# LwIP.net
KiCad netlist of a schematic drawn in Altium Designer
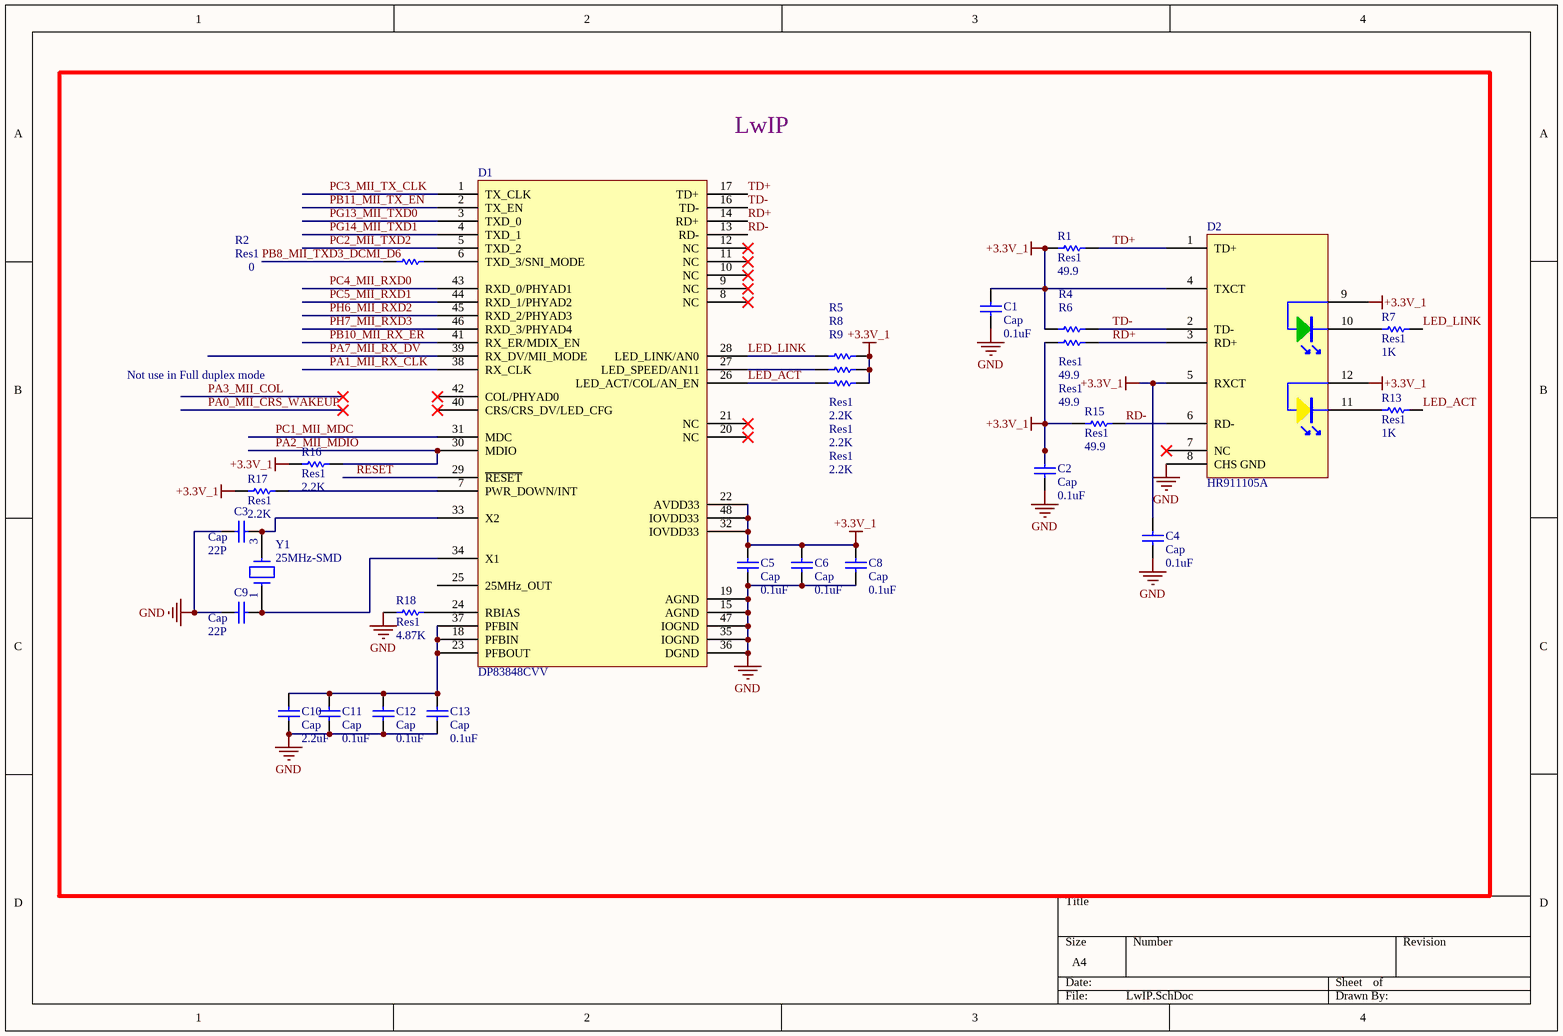
[diagram p0: LwIP.SchDoc]

(export (version "E")
  (design (tool "Eeschema 10.0.6"))
  (components
    (comp (ref "C1")
      (value "Cap")
      (footprint "0805_C")
      (description "Capacitor")
      (fields (field (name "ALTIUM_VALUE") "0.1uF") (field (name "PUBLISHER") "Altium Limited"))
      (libsource (lib "Miscellaneous Devices") (part "Cap"))
    )
    (comp (ref "C2")
      (value "Cap")
      (footprint "0805_C")
      (description "Capacitor")
      (fields (field (name "ALTIUM_VALUE") "0.1uF") (field (name "PUBLISHER") "Altium Limited"))
      (libsource (lib "Miscellaneous Devices") (part "Cap"))
    )
    (comp (ref "C3")
      (value "Cap")
      (footprint "0805_C")
      (description "Capacitor")
      (fields (field (name "ALTIUM_VALUE") "22P") (field (name "PUBLISHER") "Altium Limited"))
      (libsource (lib "Miscellaneous Devices") (part "Cap"))
    )
    (comp (ref "C4")
      (value "Cap")
      (footprint "0805_C")
      (description "Capacitor")
      (fields (field (name "ALTIUM_VALUE") "0.1uF") (field (name "PUBLISHER") "Altium Limited"))
      (libsource (lib "Miscellaneous Devices") (part "Cap"))
    )
    (comp (ref "C5")
      (value "Cap")
      (footprint "0805_C")
      (description "Capacitor")
      (fields (field (name "ALTIUM_VALUE") "0.1uF") (field (name "PUBLISHER") "Altium Limited"))
      (libsource (lib "Miscellaneous Devices") (part "Cap"))
    )
    (comp (ref "C6")
      (value "Cap")
      (footprint "0805_C")
      (description "Capacitor")
      (fields (field (name "ALTIUM_VALUE") "0.1uF") (field (name "PUBLISHER") "Altium Limited"))
      (libsource (lib "Miscellaneous Devices") (part "Cap"))
    )
    (comp (ref "C8")
      (value "Cap")
      (footprint "0805_C")
      (description "Capacitor")
      (fields (field (name "ALTIUM_VALUE") "0.1uF") (field (name "PUBLISHER") "Altium Limited"))
      (libsource (lib "Miscellaneous Devices") (part "Cap"))
    )
    (comp (ref "C9")
      (value "Cap")
      (footprint "0805_C")
      (description "Capacitor")
      (fields (field (name "ALTIUM_VALUE") "22P") (field (name "PUBLISHER") "Altium Limited"))
      (libsource (lib "Miscellaneous Devices") (part "Cap"))
    )
    (comp (ref "C10")
      (value "Cap")
      (footprint "0805_C")
      (description "Capacitor")
      (fields (field (name "ALTIUM_VALUE") "2.2uF") (field (name "PUBLISHER") "Altium Limited"))
      (libsource (lib "Miscellaneous Devices") (part "Cap"))
    )
    (comp (ref "C11")
      (value "Cap")
      (footprint "0805_C")
      (description "Capacitor")
      (fields (field (name "ALTIUM_VALUE") "0.1uF") (field (name "PUBLISHER") "Altium Limited"))
      (libsource (lib "Miscellaneous Devices") (part "Cap"))
    )
    (comp (ref "C12")
      (value "Cap")
      (footprint "0805_C")
      (description "Capacitor")
      (fields (field (name "ALTIUM_VALUE") "0.1uF") (field (name "PUBLISHER") "Altium Limited"))
      (libsource (lib "Miscellaneous Devices") (part "Cap"))
    )
    (comp (ref "C13")
      (value "Cap")
      (footprint "0805_C")
      (description "Capacitor")
      (fields (field (name "ALTIUM_VALUE") "0.1uF") (field (name "PUBLISHER") "Altium Limited"))
      (libsource (lib "Miscellaneous Devices") (part "Cap"))
    )
    (comp (ref "D1")
      (value "DP83848CVV")
      (footprint "LQFP48")
      (libsource (lib "STM32F4x9IG-Mother-B-SCH") (part "DP83848CVV"))
    )
    (comp (ref "D2")
      (value "HR911105A")
      (footprint "RJ45-LED")
      (libsource (lib "STM32F4x9IG-Mother-B-SCH") (part "HR911105A"))
    )
    (comp (ref "R1")
      (value "Res1")
      (footprint "0805_C")
      (description "Resistor")
      (fields (field (name "ALTIUM_VALUE") "49.9") (field (name "PUBLISHER") "Altium Limited"))
      (libsource (lib "Miscellaneous Devices") (part "Res1"))
    )
    (comp (ref "R2")
      (value "Res1")
      (footprint "0805_C")
      (description "Resistor")
      (fields (field (name "ALTIUM_VALUE") "0") (field (name "PUBLISHER") "Altium Limited"))
      (libsource (lib "Miscellaneous Devices") (part "Res1"))
    )
    (comp (ref "R4")
      (value "Res1")
      (footprint "0805_C")
      (description "Resistor")
      (fields (field (name "ALTIUM_VALUE") "49.9") (field (name "PUBLISHER") "Altium Limited"))
      (libsource (lib "Miscellaneous Devices") (part "Res1"))
    )
    (comp (ref "R5")
      (value "Res1")
      (footprint "0805_C")
      (description "Resistor")
      (fields (field (name "ALTIUM_VALUE") "2.2K") (field (name "PUBLISHER") "Altium Limited"))
      (libsource (lib "Miscellaneous Devices") (part "Res1"))
    )
    (comp (ref "R6")
      (value "Res1")
      (footprint "0805_C")
      (description "Resistor")
      (fields (field (name "ALTIUM_VALUE") "49.9") (field (name "PUBLISHER") "Altium Limited"))
      (libsource (lib "Miscellaneous Devices") (part "Res1"))
    )
    (comp (ref "R7")
      (value "Res1")
      (footprint "0805_C")
      (description "Resistor")
      (fields (field (name "ALTIUM_VALUE") "1K") (field (name "PUBLISHER") "Altium Limited"))
      (libsource (lib "Miscellaneous Devices") (part "Res1"))
    )
    (comp (ref "R8")
      (value "Res1")
      (footprint "0805_C")
      (description "Resistor")
      (fields (field (name "ALTIUM_VALUE") "2.2K") (field (name "PUBLISHER") "Altium Limited"))
      (libsource (lib "Miscellaneous Devices") (part "Res1"))
    )
    (comp (ref "R9")
      (value "Res1")
      (footprint "0805_C")
      (description "Resistor")
      (fields (field (name "ALTIUM_VALUE") "2.2K") (field (name "PUBLISHER") "Altium Limited"))
      (libsource (lib "Miscellaneous Devices") (part "Res1"))
    )
    (comp (ref "R13")
      (value "Res1")
      (footprint "0805_C")
      (description "Resistor")
      (fields (field (name "ALTIUM_VALUE") "1K") (field (name "PUBLISHER") "Altium Limited"))
      (libsource (lib "Miscellaneous Devices") (part "Res1"))
    )
    (comp (ref "R15")
      (value "Res1")
      (footprint "0805_C")
      (description "Resistor")
      (fields (field (name "ALTIUM_VALUE") "49.9") (field (name "PUBLISHER") "Altium Limited"))
      (libsource (lib "Miscellaneous Devices") (part "Res1"))
    )
    (comp (ref "R16")
      (value "Res1")
      (footprint "0805_C")
      (description "Resistor")
      (fields (field (name "ALTIUM_VALUE") "2.2K") (field (name "PUBLISHER") "Altium Limited"))
      (libsource (lib "Miscellaneous Devices") (part "Res1"))
    )
    (comp (ref "R17")
      (value "Res1")
      (footprint "0805_C")
      (description "Resistor")
      (fields (field (name "ALTIUM_VALUE") "2.2K") (field (name "PUBLISHER") "Altium Limited"))
      (libsource (lib "Miscellaneous Devices") (part "Res1"))
    )
    (comp (ref "R18")
      (value "Res1")
      (footprint "0805_C")
      (description "Resistor")
      (fields (field (name "ALTIUM_VALUE") "4.87K") (field (name "PUBLISHER") "Altium Limited"))
      (libsource (lib "Miscellaneous Devices") (part "Res1"))
    )
    (comp (ref "Y1")
      (value "25MHz-SMD")
      (footprint "XTAL-3225")
      (description "Crystal")
      (libsource (lib "STM32F4x9IG-Mother-B-SCH") (part "CRYSTAL-SMD"))
    )
  )
  (nets
    (net (code "1") (name "+3.3V_1") (class "Default")
      (node (ref "C1") (pin "1") (pinfunction "1_1") (pintype "passive"))
      (node (ref "C2") (pin "1") (pinfunction "1_1") (pintype "passive"))
      (node (ref "C4") (pin "1") (pinfunction "1_1") (pintype "passive"))
      (node (ref "C5") (pin "1") (pinfunction "1_1") (pintype "passive"))
      (node (ref "C6") (pin "1") (pinfunction "1_1") (pintype "passive"))
      (node (ref "C8") (pin "1") (pinfunction "1_1") (pintype "passive"))
      (node (ref "D1") (pin "22") (pinfunction "AVDD33_22") (pintype "passive"))
      (node (ref "D1") (pin "32") (pinfunction "IOVDD33_32") (pintype "passive"))
      (node (ref "D1") (pin "48") (pinfunction "IOVDD33_48") (pintype "passive"))
      (node (ref "D2") (pin "12") (pintype "passive"))
      (node (ref "D2") (pin "4") (pinfunction "TXCT_4") (pintype "passive"))
      (node (ref "D2") (pin "5") (pinfunction "RXCT_5") (pintype "passive"))
      (node (ref "D2") (pin "9") (pintype "passive"))
      (node (ref "R1") (pin "1") (pinfunction "1_1") (pintype "passive"))
      (node (ref "R15") (pin "1") (pinfunction "1_1") (pintype "passive"))
      (node (ref "R16") (pin "2") (pinfunction "2_2") (pintype "passive"))
      (node (ref "R17") (pin "2") (pinfunction "2_2") (pintype "passive"))
      (node (ref "R4") (pin "1") (pinfunction "1_1") (pintype "passive"))
      (node (ref "R5") (pin "2") (pinfunction "2_2") (pintype "passive"))
      (node (ref "R6") (pin "1") (pinfunction "1_1") (pintype "passive"))
      (node (ref "R8") (pin "2") (pinfunction "2_2") (pintype "passive"))
      (node (ref "R9") (pin "2") (pinfunction "2_2") (pintype "passive"))
    )
    (net (code "2") (name "/LED_ACT") (class "Default")
      (node (ref "D1") (pin "26") (pinfunction "LED_ACT/COL/AN_EN_26") (pintype "passive"))
      (node (ref "R13") (pin "2") (pinfunction "2_2") (pintype "passive"))
      (node (ref "R9") (pin "1") (pinfunction "1_1") (pintype "passive"))
    )
    (net (code "3") (name "/LED_LINK") (class "Default")
      (node (ref "D1") (pin "28") (pinfunction "LED_LINK/AN0_28") (pintype "passive"))
      (node (ref "R5") (pin "1") (pinfunction "1_1") (pintype "passive"))
      (node (ref "R7") (pin "2") (pinfunction "2_2") (pintype "passive"))
    )
    (net (code "5") (name "/PA1_MII_RX_CLK") (class "Default")
      (node (ref "D1") (pin "38") (pinfunction "RX_CLK_38") (pintype "passive"))
    )
    (net (code "6") (name "/PA2_MII_MDIO") (class "Default")
      (node (ref "D1") (pin "30") (pinfunction "MDIO_30") (pintype "passive"))
      (node (ref "R16") (pin "1") (pinfunction "1_1") (pintype "passive"))
    )
    (net (code "8") (name "/PA7_MII_RX_DV") (class "Default")
      (node (ref "D1") (pin "39") (pinfunction "RX_DV/MII_MODE_39") (pintype "passive"))
    )
    (net (code "9") (name "/PB8_MII_TXD3_DCMI_D6") (class "Default")
      (node (ref "R2") (pin "1") (pinfunction "1_1") (pintype "passive"))
    )
    (net (code "10") (name "/PB10_MII_RX_ER") (class "Default")
      (node (ref "D1") (pin "41") (pinfunction "RX_ER/MDIX_EN_41") (pintype "passive"))
    )
    (net (code "11") (name "/PB11_MII_TX_EN") (class "Default")
      (node (ref "D1") (pin "2") (pinfunction "TX_EN_2") (pintype "passive"))
    )
    (net (code "12") (name "/PC1_MII_MDC") (class "Default")
      (node (ref "D1") (pin "31") (pinfunction "MDC_31") (pintype "passive"))
    )
    (net (code "13") (name "/PC2_MII_TXD2") (class "Default")
      (node (ref "D1") (pin "5") (pinfunction "TXD_2_5") (pintype "passive"))
    )
    (net (code "14") (name "/PC3_MII_TX_CLK") (class "Default")
      (node (ref "D1") (pin "1") (pinfunction "TX_CLK_1") (pintype "passive"))
    )
    (net (code "15") (name "/PC4_MII_RXD0") (class "Default")
      (node (ref "D1") (pin "43") (pinfunction "RXD_0/PHYAD1_43") (pintype "passive"))
    )
    (net (code "16") (name "/PC5_MII_RXD1") (class "Default")
      (node (ref "D1") (pin "44") (pinfunction "RXD_1/PHYAD2_44") (pintype "passive"))
    )
    (net (code "17") (name "/PG13_MII_TXD0") (class "Default")
      (node (ref "D1") (pin "3") (pinfunction "TXD_0_3") (pintype "passive"))
    )
    (net (code "18") (name "/PG14_MII_TXD1") (class "Default")
      (node (ref "D1") (pin "4") (pinfunction "TXD_1_4") (pintype "passive"))
    )
    (net (code "19") (name "/PH6_MII_RXD2") (class "Default")
      (node (ref "D1") (pin "45") (pinfunction "RXD_2/PHYAD3_45") (pintype "passive"))
    )
    (net (code "20") (name "/PH7_MII_RXD3") (class "Default")
      (node (ref "D1") (pin "46") (pinfunction "RXD_3/PHYAD4_46") (pintype "passive"))
    )
    (net (code "21") (name "/RD+") (class "Default")
      (node (ref "D1") (pin "14") (pinfunction "RD+_14") (pintype "passive"))
      (node (ref "D2") (pin "3") (pinfunction "RD+_3") (pintype "passive"))
      (node (ref "R6") (pin "2") (pinfunction "2_2") (pintype "passive"))
    )
    (net (code "22") (name "/RD-") (class "Default")
      (node (ref "D1") (pin "13") (pinfunction "RD-_13") (pintype "passive"))
      (node (ref "D2") (pin "6") (pinfunction "RD-_6") (pintype "passive"))
      (node (ref "R15") (pin "2") (pinfunction "2_2") (pintype "passive"))
    )
    (net (code "23") (name "/RESET") (class "Default")
      (node (ref "D1") (pin "29") (pinfunction "~{RESET}_29") (pintype "passive"))
    )
    (net (code "24") (name "/TD+") (class "Default")
      (node (ref "D1") (pin "17") (pinfunction "TD+_17") (pintype "passive"))
      (node (ref "D2") (pin "1") (pinfunction "TD+_1") (pintype "passive"))
      (node (ref "R1") (pin "2") (pinfunction "2_2") (pintype "passive"))
    )
    (net (code "25") (name "/TD-") (class "Default")
      (node (ref "D1") (pin "16") (pinfunction "TD-_16") (pintype "passive"))
      (node (ref "D2") (pin "2") (pinfunction "TD-_2") (pintype "passive"))
      (node (ref "R4") (pin "2") (pinfunction "2_2") (pintype "passive"))
    )
    (net (code "26") (name "GND") (class "Default")
      (node (ref "C1") (pin "2") (pinfunction "2_2") (pintype "passive"))
      (node (ref "C10") (pin "2") (pinfunction "2_2") (pintype "passive"))
      (node (ref "C11") (pin "2") (pinfunction "2_2") (pintype "passive"))
      (node (ref "C12") (pin "2") (pinfunction "2_2") (pintype "passive"))
      (node (ref "C13") (pin "2") (pinfunction "2_2") (pintype "passive"))
      (node (ref "C2") (pin "2") (pinfunction "2_2") (pintype "passive"))
      (node (ref "C3") (pin "1") (pinfunction "1_1") (pintype "passive"))
      (node (ref "C4") (pin "2") (pinfunction "2_2") (pintype "passive"))
      (node (ref "C5") (pin "2") (pinfunction "2_2") (pintype "passive"))
      (node (ref "C6") (pin "2") (pinfunction "2_2") (pintype "passive"))
      (node (ref "C8") (pin "2") (pinfunction "2_2") (pintype "passive"))
      (node (ref "C9") (pin "1") (pinfunction "1_1") (pintype "passive"))
      (node (ref "D1") (pin "15") (pinfunction "AGND_15") (pintype "passive"))
      (node (ref "D1") (pin "19") (pinfunction "AGND_19") (pintype "passive"))
      (node (ref "D1") (pin "35") (pinfunction "IOGND_35") (pintype "passive"))
      (node (ref "D1") (pin "36") (pinfunction "DGND_36") (pintype "passive"))
      (node (ref "D1") (pin "47") (pinfunction "IOGND_47") (pintype "passive"))
      (node (ref "D2") (pin "8") (pinfunction "CHS_GND_8") (pintype "passive"))
      (node (ref "R18") (pin "2") (pinfunction "2_2") (pintype "passive"))
    )
    (net (code "27") (name "Net-(D1-LED_SPEED{slash}AN11)") (class "Default")
      (node (ref "D1") (pin "27") (pinfunction "LED_SPEED/AN11_27") (pintype "passive"))
      (node (ref "R8") (pin "1") (pinfunction "1_1") (pintype "passive"))
    )
    (net (code "28") (name "Net-(D1-PFBOUT)") (class "Default")
      (node (ref "C10") (pin "1") (pinfunction "1_1") (pintype "passive"))
      (node (ref "C11") (pin "1") (pinfunction "1_1") (pintype "passive"))
      (node (ref "C12") (pin "1") (pinfunction "1_1") (pintype "passive"))
      (node (ref "C13") (pin "1") (pinfunction "1_1") (pintype "passive"))
      (node (ref "D1") (pin "18") (pinfunction "PFBIN_18") (pintype "passive"))
      (node (ref "D1") (pin "23") (pinfunction "PFBOUT_23") (pintype "passive"))
      (node (ref "D1") (pin "37") (pinfunction "PFBIN_37") (pintype "passive"))
    )
    (net (code "29") (name "Net-(D1-PWR_DOWN{slash}INT)") (class "Default")
      (node (ref "D1") (pin "7") (pinfunction "PWR_DOWN/INT_7") (pintype "passive"))
      (node (ref "R17") (pin "1") (pinfunction "1_1") (pintype "passive"))
    )
    (net (code "30") (name "Net-(D1-RBIAS)") (class "Default")
      (node (ref "D1") (pin "24") (pinfunction "RBIAS_24") (pintype "passive"))
      (node (ref "R18") (pin "1") (pinfunction "1_1") (pintype "passive"))
    )
    (net (code "31") (name "Net-(D1-TXD_3{slash}SNI_MODE)") (class "Default")
      (node (ref "D1") (pin "6") (pinfunction "TXD_3/SNI_MODE_6") (pintype "passive"))
      (node (ref "R2") (pin "2") (pinfunction "2_2") (pintype "passive"))
    )
    (net (code "32") (name "Net-(D1-X1)") (class "Default")
      (node (ref "C9") (pin "2") (pinfunction "2_2") (pintype "passive"))
      (node (ref "D1") (pin "34") (pinfunction "X1_34") (pintype "passive"))
      (node (ref "Y1") (pin "1") (pinfunction "1_1") (pintype "passive"))
    )
    (net (code "33") (name "Net-(D1-X2)") (class "Default")
      (node (ref "C3") (pin "2") (pinfunction "2_2") (pintype "passive"))
      (node (ref "D1") (pin "33") (pinfunction "X2_33") (pintype "passive"))
      (node (ref "Y1") (pin "3") (pinfunction "3_3") (pintype "passive"))
    )
    (net (code "34") (name "Net-(D2-Pad10)") (class "Default")
      (node (ref "D2") (pin "10") (pintype "passive"))
      (node (ref "R7") (pin "1") (pinfunction "1_1") (pintype "passive"))
    )
    (net (code "35") (name "Net-(D2-Pad11)") (class "Default")
      (node (ref "D2") (pin "11") (pintype "passive"))
      (node (ref "R13") (pin "1") (pinfunction "1_1") (pintype "passive"))
    )
    (net (code "36") (name "unconnected-(D1-25MHz_OUT-Pad25)") (class "Default")
      (node (ref "D1") (pin "25") (pinfunction "25MHz_OUT_25") (pintype "passive"))
    )
    (net (code "37") (name "unconnected-(D1-COL{slash}PHYAD0-Pad42)") (class "Default")
      (node (ref "D1") (pin "42") (pinfunction "COL/PHYAD0_42") (pintype "passive+no_connect"))
    )
    (net (code "38") (name "unconnected-(D1-CRS{slash}CRS_DV{slash}LED_CFG-Pad40)") (class "Default")
      (node (ref "D1") (pin "40") (pinfunction "CRS/CRS_DV/LED_CFG_40") (pintype "passive+no_connect"))
    )
    (net (code "39") (name "unconnected-(D1-NC-Pad8)") (class "Default")
      (node (ref "D1") (pin "8") (pinfunction "NC_8") (pintype "passive+no_connect"))
    )
    (net (code "40") (name "unconnected-(D1-NC-Pad9)") (class "Default")
      (node (ref "D1") (pin "9") (pinfunction "NC_9") (pintype "passive+no_connect"))
    )
    (net (code "41") (name "unconnected-(D1-NC-Pad10)") (class "Default")
      (node (ref "D1") (pin "10") (pinfunction "NC_10") (pintype "passive+no_connect"))
    )
    (net (code "42") (name "unconnected-(D1-NC-Pad11)") (class "Default")
      (node (ref "D1") (pin "11") (pinfunction "NC_11") (pintype "passive+no_connect"))
    )
    (net (code "43") (name "unconnected-(D1-NC-Pad12)") (class "Default")
      (node (ref "D1") (pin "12") (pinfunction "NC_12") (pintype "passive+no_connect"))
    )
    (net (code "44") (name "unconnected-(D1-NC-Pad20)") (class "Default")
      (node (ref "D1") (pin "20") (pinfunction "NC_20") (pintype "passive+no_connect"))
    )
    (net (code "45") (name "unconnected-(D1-NC-Pad21)") (class "Default")
      (node (ref "D1") (pin "21") (pinfunction "NC_21") (pintype "passive+no_connect"))
    )
    (net (code "46") (name "unconnected-(D2-NC-Pad7)") (class "Default")
      (node (ref "D2") (pin "7") (pinfunction "NC_7") (pintype "passive+no_connect"))
    )
  )
)
